# VCA.net
KiCad netlist of a schematic drawn in Altium Designer
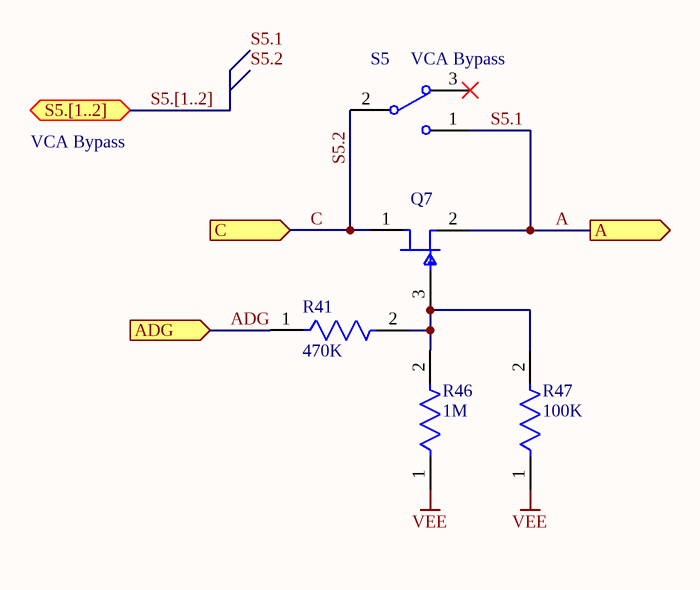
[diagram p0: VCA.SchDoc]

(export (version "E")
  (design (tool "Eeschema 10.0.6"))
  (components
    (comp (ref "Q7")
      (value "MMBFJ113")
      (footprint "FP-318BM-IPC_C")
      (description "JFET N-CH 35V 350MW SOT23")
      (fields
        (field (name "MANUFACTURER") "ON Semiconductor")
        (field (name "OCTOPART") "https://octopart.com/mmbfj113-on+semiconductor-84330253")
      )
      (libsource (lib "Altium Content Vault") (part "14398f7355be6f33287877db3ee21c7"))
    )
    (comp (ref "R41")
      (value "ESR03EZPJ474")
      (footprint "FP-ESR03-IPC_B")
      (description "470kΩ ±5% 0.25W 0603 Anti-Surge Chip Resistor AEC-Q200")
      (fields (field (name "TOLERANCE") "5%") (field (name "RESISTANCE") "470K"))
      (libsource (lib "Altium Content Vault") (part "1029c3af85768c4190bb7ad29bc67b5"))
    )
    (comp (ref "R46")
      (value "ESR03EZPJ105")
      (footprint "FP-ESR03-IPC_B")
      (description "1MΩ ±5% 0.25W 0603 Anti-Surge Chip Resistor AEC-Q200")
      (fields (field (name "RESISTANCE") "1M") (field (name "TOLERANCE") "5%"))
      (libsource (lib "Altium Content Vault") (part "1029c3af85768c4190bb7ad29bc67b5"))
    )
    (comp (ref "R47")
      (value "ESR03EZPJ104")
      (footprint "FP-ESR03-IPC_B")
      (description "100kΩ ±5% 0.25W 0603 Anti-Surge Chip Resistor AEC-Q200")
      (fields (field (name "TOLERANCE") "5%") (field (name "RESISTANCE") "100K"))
      (libsource (lib "Altium Content Vault") (part "1029c3af85768c4190bb7ad29bc67b5"))
    )
    (comp (ref "S5")
      (value "VCA Bypass")
      (footprint "HDR1X3")
      (description "Switch Toggle ON None ON SPDT Round Lever Solder Lug 5A 250VAC 28VDC Panel Mount with Threads")
      (fields
        (field (name "MANUFACTURER") "E-Switch")
        (field (name "MANUFACTURER PART NUMBER") "100SP1T1B1M1QEH")
      )
      (libsource (lib "Miscellaneous Devices") (part "SW-SPDT"))
    )
  )
  (nets
    (net (code "1") (name "/ADG") (class "Default")
      (node (ref "R41") (pin "1") (pinfunction "1_1") (pintype "passive"))
    )
    (net (code "2") (name "/S5.1") (class "Default")
      (node (ref "Q7") (pin "2") (pinfunction "S_2") (pintype "passive"))
      (node (ref "S5") (pin "1") (pinfunction "1_1") (pintype "passive"))
    )
    (net (code "3") (name "/S5.2") (class "Default")
      (node (ref "Q7") (pin "1") (pinfunction "D_1") (pintype "passive"))
      (node (ref "S5") (pin "2") (pinfunction "2_2") (pintype "passive"))
    )
    (net (code "5") (name "Net-(Q7-G)") (class "Default")
      (node (ref "Q7") (pin "3") (pinfunction "G_3") (pintype "passive"))
      (node (ref "R41") (pin "2") (pinfunction "2_2") (pintype "passive"))
      (node (ref "R46") (pin "2") (pinfunction "2_2") (pintype "passive"))
      (node (ref "R47") (pin "2") (pinfunction "2_2") (pintype "passive"))
    )
    (net (code "6") (name "VEE") (class "Default")
      (node (ref "R46") (pin "1") (pinfunction "1_1") (pintype "passive"))
      (node (ref "R47") (pin "1") (pinfunction "1_1") (pintype "passive"))
    )
    (net (code "7") (name "unconnected-(S5-Pad3)") (class "Default")
      (node (ref "S5") (pin "3") (pinfunction "3_3") (pintype "passive+no_connect"))
    )
  )
)
